# Hermit_Board_Rev_A6.net
KiCad netlist of a schematic drawn in EAGLE
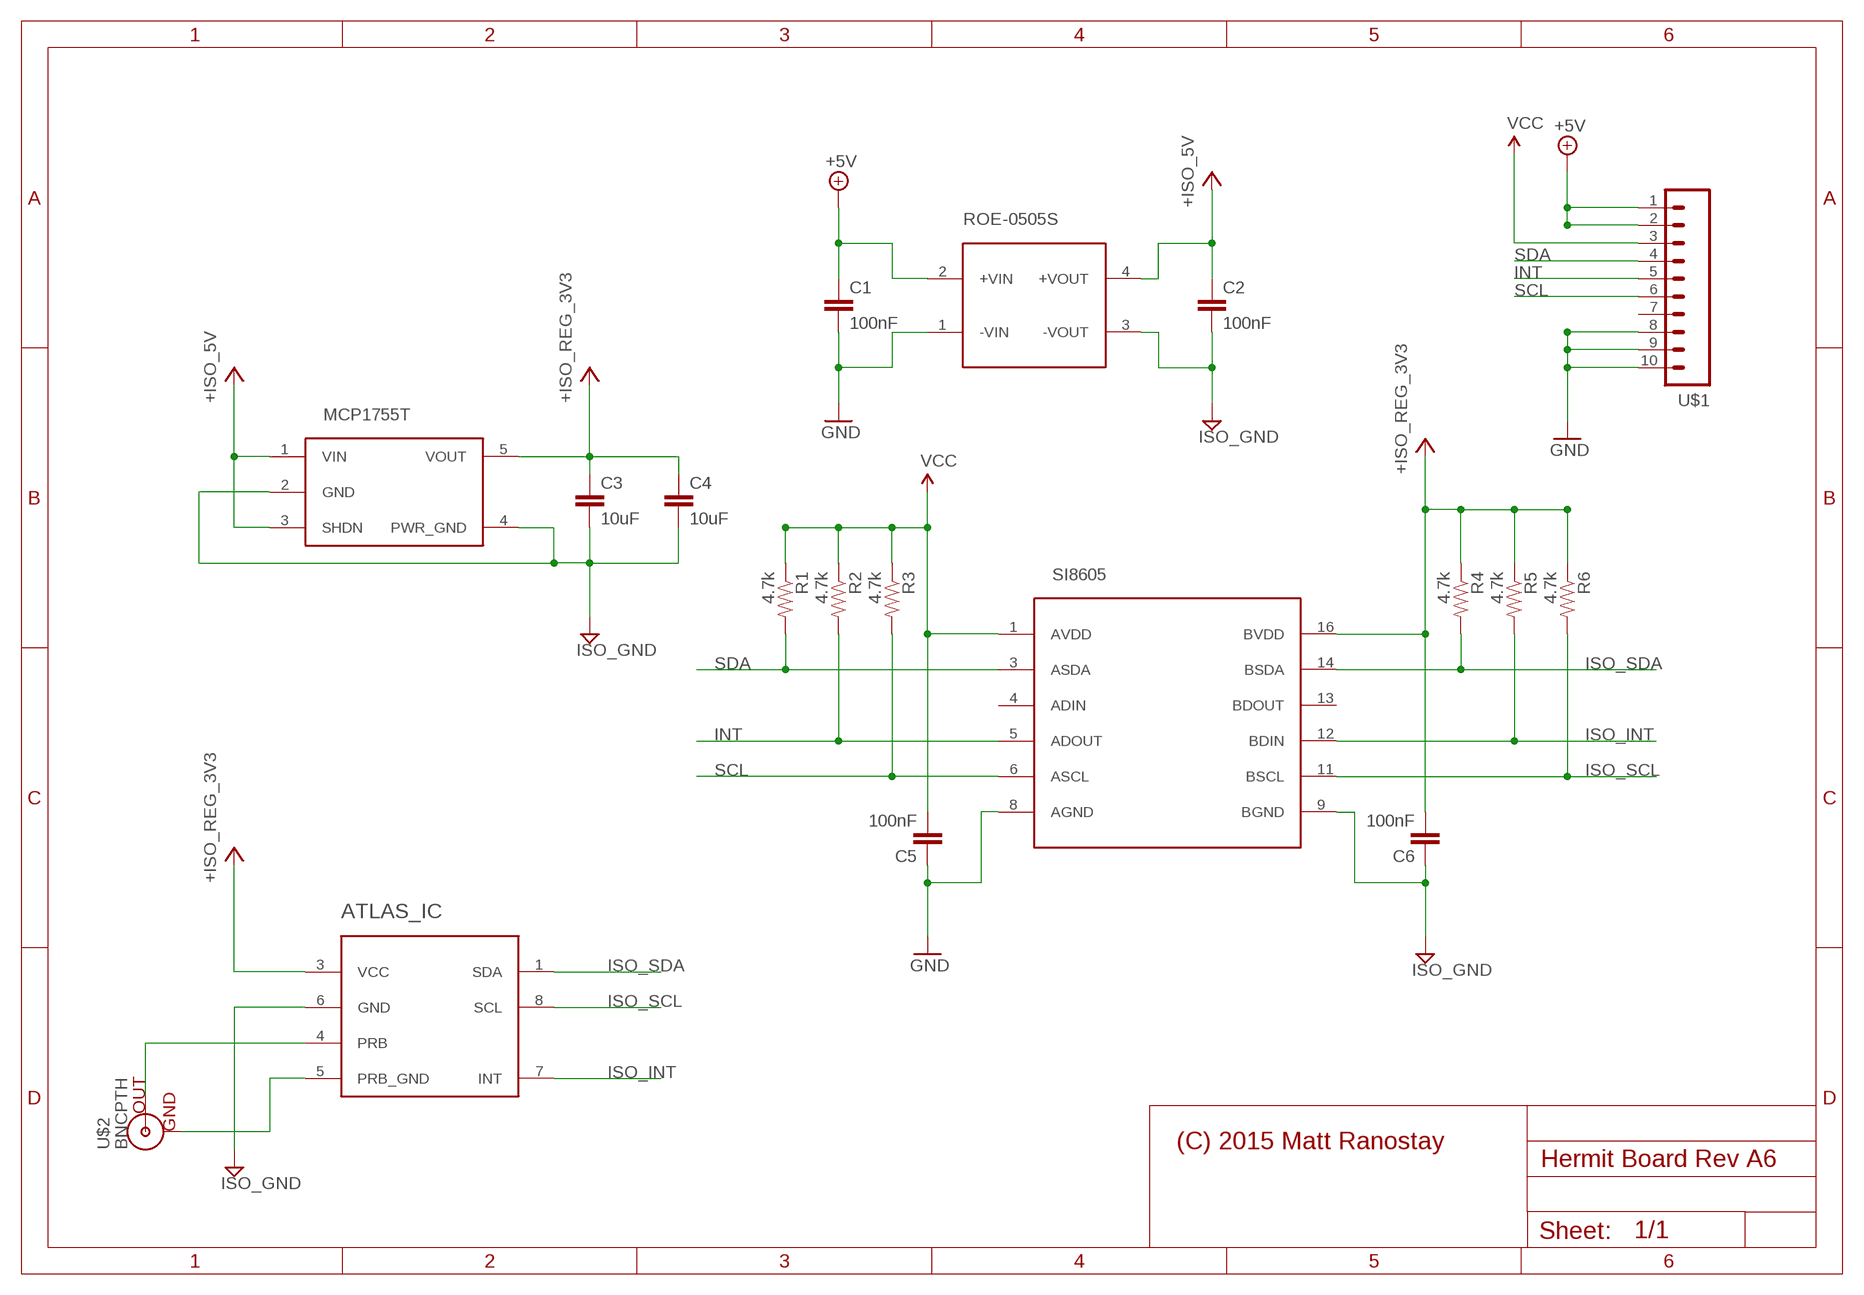
[diagram p0: schematic, sheet 1]

(export (version "E")
  (design (tool "Eeschema 10.0.6"))
  (components
    (comp (ref "ATLAS_IC")
      (value "ATLAS-OEM")
      (footprint "eagle-import:ATLAS-OEM")
      (libsource (lib "eagle-import") (part "ATLAS-OEM"))
    )
    (comp (ref "C1")
      (value "100nF")
      (footprint "eagle-import:0805")
      (libsource (lib "eagle-import") (part "CAP0805"))
    )
    (comp (ref "C2")
      (value "100nF")
      (footprint "eagle-import:0805")
      (libsource (lib "eagle-import") (part "CAP0805"))
    )
    (comp (ref "C3")
      (value "10uF")
      (footprint "eagle-import:0805")
      (libsource (lib "eagle-import") (part "CAP0805"))
    )
    (comp (ref "C4")
      (value "10uF")
      (footprint "eagle-import:0805")
      (libsource (lib "eagle-import") (part "CAP0805"))
    )
    (comp (ref "C5")
      (value "100nF")
      (footprint "eagle-import:0805")
      (libsource (lib "eagle-import") (part "CAP0805"))
    )
    (comp (ref "C6")
      (value "100nF")
      (footprint "eagle-import:0805")
      (libsource (lib "eagle-import") (part "CAP0805"))
    )
    (comp (ref "MCP1755T")
      (value "MCP1755T")
      (footprint "eagle-import:SOT-23-5")
      (libsource (lib "eagle-import") (part "MCP1755T"))
    )
    (comp (ref "R1")
      (value "4.7k")
      (footprint "eagle-import:0805")
      (libsource (lib "eagle-import") (part "RESISTOR0805-RES"))
    )
    (comp (ref "R2")
      (value "4.7k")
      (footprint "eagle-import:0805")
      (libsource (lib "eagle-import") (part "RESISTOR0805-RES"))
    )
    (comp (ref "R3")
      (value "4.7k")
      (footprint "eagle-import:0805")
      (libsource (lib "eagle-import") (part "RESISTOR0805-RES"))
    )
    (comp (ref "R4")
      (value "4.7k")
      (footprint "eagle-import:0805")
      (libsource (lib "eagle-import") (part "RESISTOR0805-RES"))
    )
    (comp (ref "R5")
      (value "4.7k")
      (footprint "eagle-import:0805")
      (libsource (lib "eagle-import") (part "RESISTOR0805-RES"))
    )
    (comp (ref "R6")
      (value "4.7k")
      (footprint "eagle-import:0805")
      (libsource (lib "eagle-import") (part "RESISTOR0805-RES"))
    )
    (comp (ref "ROE-0505S")
      (value "ROE-0505S")
      (footprint "eagle-import:SIP4")
      (libsource (lib "eagle-import") (part "ROE-0505S"))
    )
    (comp (ref "SI8605")
      (value "SI8605")
      (footprint "eagle-import:SOIC16-1.27-10X3.9MM")
      (libsource (lib "eagle-import") (part "SI8605"))
    )
    (comp (ref "U$1")
      (value "M10SILK_FEMALE_PTH")
      (footprint "eagle-import:1X10")
      (libsource (lib "eagle-import") (part "M10SILK_FEMALE_PTH"))
    )
    (comp (ref "U$2")
      (value "BNCPTH")
      (footprint "eagle-import:BNC")
      (libsource (lib "eagle-import") (part "BNCPTH"))
    )
  )
  (nets
    (net (code "1") (name "+5V") (class "Default")
      (node (ref "C1") (pin "1") (pinfunction "1_1") (pintype "passive"))
      (node (ref "ROE-0505S") (pin "2") (pinfunction "+VIN_2") (pintype "power_in"))
      (node (ref "U$1") (pin "1") (pinfunction "1_1") (pintype "passive"))
      (node (ref "U$1") (pin "2") (pinfunction "2_2") (pintype "passive"))
    )
    (net (code "2") (name "+ISO_5V") (class "Default")
      (node (ref "C2") (pin "1") (pinfunction "1_1") (pintype "passive"))
      (node (ref "MCP1755T") (pin "1") (pinfunction "VIN_1") (pintype "power_in"))
      (node (ref "MCP1755T") (pin "3") (pinfunction "SHDN_3") (pintype "input"))
      (node (ref "ROE-0505S") (pin "4") (pinfunction "+VOUT_4") (pintype "power_in"))
    )
    (net (code "3") (name "+ISO_REG_3V3") (class "Default")
      (node (ref "ATLAS_IC") (pin "3") (pinfunction "VCC_3") (pintype "power_in"))
      (node (ref "C3") (pin "1") (pinfunction "1_1") (pintype "passive"))
      (node (ref "C4") (pin "1") (pinfunction "1_1") (pintype "passive"))
      (node (ref "C6") (pin "2") (pinfunction "2_2") (pintype "passive"))
      (node (ref "MCP1755T") (pin "5") (pinfunction "VOUT_5") (pintype "power_in"))
      (node (ref "R4") (pin "1") (pinfunction "1_1") (pintype "passive"))
      (node (ref "R5") (pin "1") (pinfunction "1_1") (pintype "passive"))
      (node (ref "R6") (pin "1") (pinfunction "1_1") (pintype "passive"))
      (node (ref "SI8605") (pin "16") (pinfunction "BVDD_16") (pintype "power_in"))
    )
    (net (code "4") (name "/INT") (class "Default")
      (node (ref "R2") (pin "2") (pinfunction "2_2") (pintype "passive"))
      (node (ref "SI8605") (pin "5") (pinfunction "ADOUT_5") (pintype "output"))
      (node (ref "U$1") (pin "5") (pinfunction "5_5") (pintype "passive"))
    )
    (net (code "5") (name "/ISO_INT") (class "Default")
      (node (ref "ATLAS_IC") (pin "7") (pinfunction "INT_7") (pintype "output"))
      (node (ref "R5") (pin "2") (pinfunction "2_2") (pintype "passive"))
      (node (ref "SI8605") (pin "12") (pinfunction "BDIN_12") (pintype "input"))
    )
    (net (code "6") (name "/ISO_SCL") (class "Default")
      (node (ref "ATLAS_IC") (pin "8") (pinfunction "SCL_8") (pintype "bidirectional"))
      (node (ref "R6") (pin "2") (pinfunction "2_2") (pintype "passive"))
      (node (ref "SI8605") (pin "11") (pinfunction "BSCL_11") (pintype "bidirectional"))
    )
    (net (code "7") (name "/ISO_SDA") (class "Default")
      (node (ref "ATLAS_IC") (pin "1") (pinfunction "SDA_1") (pintype "bidirectional"))
      (node (ref "R4") (pin "2") (pinfunction "2_2") (pintype "passive"))
      (node (ref "SI8605") (pin "14") (pinfunction "BSDA_14") (pintype "bidirectional"))
    )
    (net (code "8") (name "/SCL") (class "Default")
      (node (ref "R3") (pin "2") (pinfunction "2_2") (pintype "passive"))
      (node (ref "SI8605") (pin "6") (pinfunction "ASCL_6") (pintype "bidirectional"))
      (node (ref "U$1") (pin "6") (pinfunction "6_6") (pintype "passive"))
    )
    (net (code "9") (name "/SDA") (class "Default")
      (node (ref "R1") (pin "2") (pinfunction "2_2") (pintype "passive"))
      (node (ref "SI8605") (pin "3") (pinfunction "ASDA_3") (pintype "bidirectional"))
      (node (ref "U$1") (pin "4") (pinfunction "4_4") (pintype "passive"))
    )
    (net (code "10") (name "GND") (class "Default")
      (node (ref "C1") (pin "2") (pinfunction "2_2") (pintype "passive"))
      (node (ref "C5") (pin "1") (pinfunction "1_1") (pintype "passive"))
      (node (ref "ROE-0505S") (pin "1") (pinfunction "-VIN_1") (pintype "power_in"))
      (node (ref "SI8605") (pin "8") (pinfunction "AGND_8") (pintype "power_in"))
      (node (ref "U$1") (pin "10") (pinfunction "10_10") (pintype "passive"))
      (node (ref "U$1") (pin "8") (pinfunction "8_8") (pintype "passive"))
      (node (ref "U$1") (pin "9") (pinfunction "9_9") (pintype "passive"))
    )
    (net (code "11") (name "ISO_GND") (class "Default")
      (node (ref "ATLAS_IC") (pin "6") (pinfunction "GND_6") (pintype "power_in"))
      (node (ref "C2") (pin "2") (pinfunction "2_2") (pintype "passive"))
      (node (ref "C3") (pin "2") (pinfunction "2_2") (pintype "passive"))
      (node (ref "C4") (pin "2") (pinfunction "2_2") (pintype "passive"))
      (node (ref "C6") (pin "1") (pinfunction "1_1") (pintype "passive"))
      (node (ref "MCP1755T") (pin "2") (pinfunction "GND_2") (pintype "power_in"))
      (node (ref "MCP1755T") (pin "4") (pinfunction "PWR_GND_4") (pintype "power_in"))
      (node (ref "ROE-0505S") (pin "3") (pinfunction "-VOUT_3") (pintype "power_in"))
      (node (ref "SI8605") (pin "9") (pinfunction "BGND_9") (pintype "power_in"))
    )
    (net (code "12") (name "Net-(ATLAS_IC-PRB)") (class "Default")
      (node (ref "ATLAS_IC") (pin "4") (pinfunction "PRB_4") (pintype "input"))
      (node (ref "U$2") (pin "S") (pinfunction "OUT_S") (pintype "bidirectional"))
    )
    (net (code "13") (name "Net-(ATLAS_IC-PRB_GND)") (class "Default")
      (node (ref "ATLAS_IC") (pin "5") (pinfunction "PRB_GND_5") (pintype "power_in"))
      (node (ref "U$2") (pin "GND") (pinfunction "GND_GND") (pintype "bidirectional"))
    )
    (net (code "14") (name "VCC") (class "Default")
      (node (ref "C5") (pin "2") (pinfunction "2_2") (pintype "passive"))
      (node (ref "R1") (pin "1") (pinfunction "1_1") (pintype "passive"))
      (node (ref "R2") (pin "1") (pinfunction "1_1") (pintype "passive"))
      (node (ref "R3") (pin "1") (pinfunction "1_1") (pintype "passive"))
      (node (ref "SI8605") (pin "1") (pinfunction "AVDD_1") (pintype "power_in"))
      (node (ref "U$1") (pin "3") (pinfunction "3_3") (pintype "passive"))
    )
    (net (code "15") (name "unconnected-(SI8605-ADIN-Pad4)") (class "Default")
      (node (ref "SI8605") (pin "4") (pinfunction "ADIN_4") (pintype "input"))
    )
    (net (code "16") (name "unconnected-(SI8605-BDOUT-Pad13)") (class "Default")
      (node (ref "SI8605") (pin "13") (pinfunction "BDOUT_13") (pintype "output"))
    )
    (net (code "17") (name "unconnected-(U$1-Pad7)") (class "Default")
      (node (ref "U$1") (pin "7") (pinfunction "7_7") (pintype "passive"))
    )
  )
)
